# PAGE2.net
KiCad netlist of a schematic drawn in Altium Designer
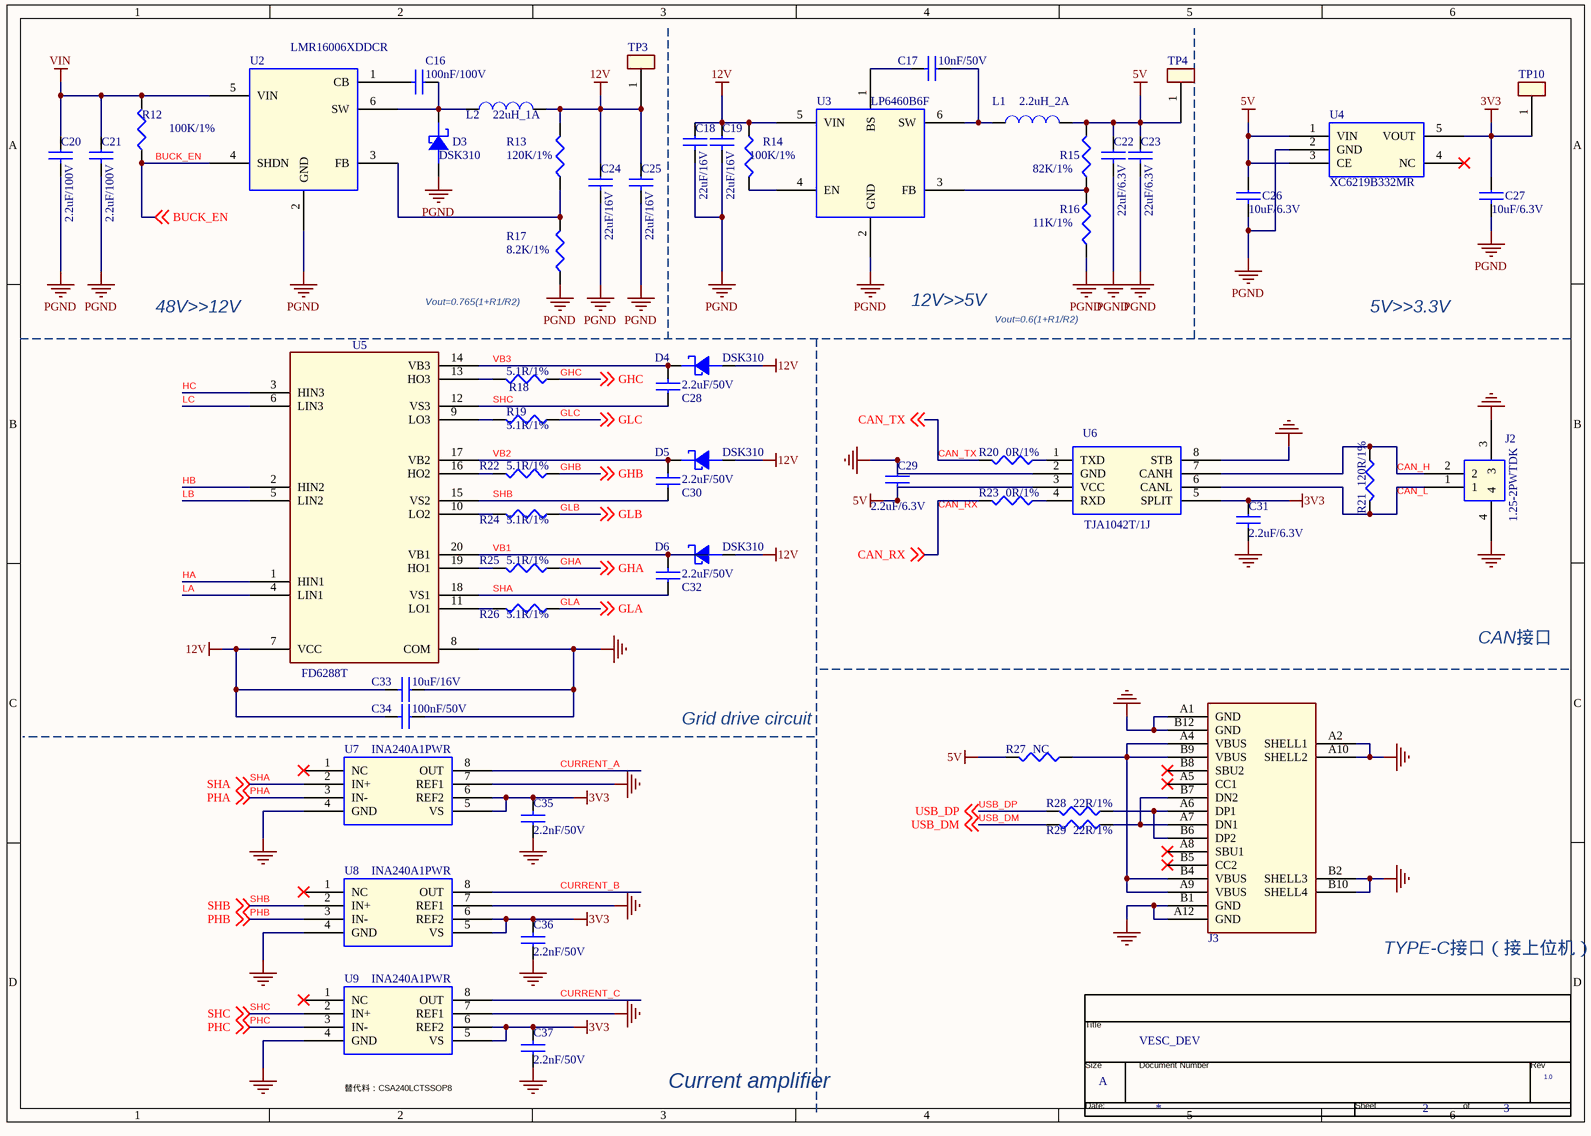
[diagram p0: PAGE2.SchDoc]

(export (version "E")
  (design (tool "Eeschema 10.0.6"))
  (components
    (comp (ref "*")
      (value "TitleBlock0")
      (fields
        (field (name "PAGE COUNT") "3")
        (field (name "PAGE NUMBER") "2")
        (field (name "PAGE SIZE") "A")
        (field (name "TITLE") "VESC_DEV")
        (field (name "REVCODE") "1.0")
      )
      (libsource (lib "*") (part "TitleBlock0"))
    )
    (comp (ref "C16") (value "100nF/100V") (footprint "C0603") (libsource (lib "*") (part "CAP NP")))
    (comp (ref "C17") (value "10nF/50V") (footprint "C0402") (libsource (lib "*") (part "CAP NP")))
    (comp (ref "C18") (value "22uF/16V") (footprint "C0805") (libsource (lib "*") (part "CAP NP")))
    (comp (ref "C19") (value "22uF/16V") (footprint "C0805") (libsource (lib "*") (part "CAP NP")))
    (comp (ref "C20") (value "2.2uF/100V") (footprint "C1206") (libsource (lib "*") (part "CAP NP")))
    (comp (ref "C21") (value "2.2uF/100V") (footprint "C1206") (libsource (lib "*") (part "CAP NP")))
    (comp (ref "C22") (value "22uF/6.3V") (footprint "C0805") (libsource (lib "*") (part "CAP NP")))
    (comp (ref "C23") (value "22uF/6.3V") (footprint "C0805") (libsource (lib "*") (part "CAP NP")))
    (comp (ref "C24") (value "22uF/16V") (footprint "C0805") (libsource (lib "*") (part "CAP NP")))
    (comp (ref "C25") (value "22uF/16V") (footprint "C0805") (libsource (lib "*") (part "CAP NP")))
    (comp (ref "C26") (value "10uF/6.3V") (footprint "C0402") (libsource (lib "*") (part "CAP NP")))
    (comp (ref "C27") (value "10uF/6.3V") (footprint "C0402") (libsource (lib "*") (part "CAP NP")))
    (comp (ref "C28") (value "2.2uF/50V") (footprint "C0603") (libsource (lib "*") (part "CAP NP")))
    (comp (ref "C29") (value "2.2uF/6.3V") (footprint "C0402") (libsource (lib "*") (part "CAP NP")))
    (comp (ref "C30") (value "2.2uF/50V") (footprint "C0603") (libsource (lib "*") (part "CAP NP")))
    (comp (ref "C31") (value "2.2uF/6.3V") (footprint "C0402") (libsource (lib "*") (part "CAP NP")))
    (comp (ref "C32") (value "2.2uF/50V") (footprint "C0603") (libsource (lib "*") (part "CAP NP")))
    (comp (ref "C33") (value "10uF/16V") (footprint "C0603") (libsource (lib "*") (part "CAP NP")))
    (comp (ref "C34") (value "100nF/50V") (footprint "C0402") (libsource (lib "*") (part "CAP NP")))
    (comp (ref "C35") (value "2.2nF/50V") (footprint "C0402") (libsource (lib "*") (part "CAP NP")))
    (comp (ref "C36") (value "2.2nF/50V") (footprint "C0402") (libsource (lib "*") (part "CAP NP")))
    (comp (ref "C37") (value "2.2nF/50V") (footprint "C0402") (libsource (lib "*") (part "CAP NP")))
    (comp (ref "D3") (value "DSK310") (footprint "SOD-123F") (libsource (lib "*") (part "DIODE SCHOTTKY21")))
    (comp (ref "D4") (value "DSK310") (footprint "SOD-123F") (libsource (lib "*") (part "DIODE SCHOTTKY21")))
    (comp (ref "D5") (value "DSK310") (footprint "SOD-123F") (libsource (lib "*") (part "DIODE SCHOTTKY21")))
    (comp (ref "D6") (value "DSK310") (footprint "SOD-123F") (libsource (lib "*") (part "DIODE SCHOTTKY21")))
    (comp (ref "J2")
      (value "1.25-2PWTDK")
      (footprint "SMD-2P-1_25")
      (libsource (lib "*") (part "1.25-2PWTDK"))
    )
    (comp (ref "J3")
      (value "TYPE-C 16PLC-H10.0")
      (footprint "TYPE-C-TH_16PLC-H10.0")
      (description "连接器类型:Type-C;标准:USB 3.1;公母:母;安装方式:直插;触点数量:16P;端口数量:1;额定电流 - 电源:5A;触头材质:-;触头镀层:-;工作温度范围:-40℃~+85℃;")
      (fields (field (name "MANUFACTURER") "SHOU HAN(首韩)"))
      (libsource (lib "VESC_DEVICE_Library") (part "TYPE-C 16PLC-H10.0"))
    )
    (comp (ref "L1") (value "2.2uH_2A") (footprint "L4020") (libsource (lib "*") (part "INDUCTOR")))
    (comp (ref "L2") (value "22uH_1A") (footprint "L4020") (libsource (lib "*") (part "INDUCTOR")))
    (comp (ref "R12") (value "100K/1%") (footprint "R0402") (libsource (lib "*") (part "RESISTOR")))
    (comp (ref "R13") (value "120K/1%") (footprint "R0402") (libsource (lib "*") (part "RESISTOR")))
    (comp (ref "R14") (value "100K/1%") (footprint "R0402") (libsource (lib "*") (part "RESISTOR")))
    (comp (ref "R15") (value "82K/1%") (footprint "R0402") (libsource (lib "*") (part "RESISTOR")))
    (comp (ref "R16") (value "11K/1%") (footprint "R0402") (libsource (lib "*") (part "RESISTOR")))
    (comp (ref "R17") (value "8.2K/1%") (footprint "R0402") (libsource (lib "*") (part "RESISTOR")))
    (comp (ref "R18") (value "5.1R/1%") (footprint "R0402") (libsource (lib "*") (part "RESISTOR")))
    (comp (ref "R19") (value "5.1R/1%") (footprint "R0402") (libsource (lib "*") (part "RESISTOR")))
    (comp (ref "R20") (value "0R/1%") (footprint "R0402") (libsource (lib "*") (part "RESISTOR")))
    (comp (ref "R21") (value "120R/1%") (footprint "R0402") (libsource (lib "*") (part "RESISTOR")))
    (comp (ref "R22") (value "5.1R/1%") (footprint "R0402") (libsource (lib "*") (part "RESISTOR")))
    (comp (ref "R23") (value "0R/1%") (footprint "R0402") (libsource (lib "*") (part "RESISTOR")))
    (comp (ref "R24") (value "5.1R/1%") (footprint "R0402") (libsource (lib "*") (part "RESISTOR")))
    (comp (ref "R25") (value "5.1R/1%") (footprint "R0402") (libsource (lib "*") (part "RESISTOR")))
    (comp (ref "R26") (value "5.1R/1%") (footprint "R0402") (libsource (lib "*") (part "RESISTOR")))
    (comp (ref "R27") (value "NC") (footprint "R0603") (libsource (lib "*") (part "RESISTOR")))
    (comp (ref "R28") (value "22R/1%") (footprint "R0402") (libsource (lib "*") (part "RESISTOR")))
    (comp (ref "R29") (value "22R/1%") (footprint "R0402") (libsource (lib "*") (part "RESISTOR")))
    (comp (ref "TP3")
      (value "TEST POINT")
      (footprint "test_point_100_smd")
      (libsource (lib "VESC_DEVICE_Library") (part "TEST POINT"))
    )
    (comp (ref "TP4")
      (value "TEST POINT")
      (footprint "test_point_100_smd")
      (libsource (lib "VESC_DEVICE_Library") (part "TEST POINT"))
    )
    (comp (ref "TP10")
      (value "TEST POINT")
      (footprint "test_point_100_smd")
      (libsource (lib "VESC_DEVICE_Library") (part "TEST POINT"))
    )
    (comp (ref "U2")
      (value "LMR16006XDDCR")
      (footprint "SOT-23-6")
      (libsource (lib "*") (part "LMR16006XDDCR"))
    )
    (comp (ref "U3") (value "LP6460B6F") (footprint "SOT-23-6") (libsource (lib "*") (part "LP6460B6F")))
    (comp (ref "U4")
      (value "XC6219B332MR")
      (footprint "SOT-23-5")
      (libsource (lib "*") (part "XC6219B332MR"))
    )
    (comp (ref "U5")
      (value "FD6288T")
      (footprint "TSSOP-20")
      (libsource (lib "VESC_DEVICE_Library") (part "FD6288T"))
    )
    (comp (ref "U6") (value "TJA1042T/1J") (footprint "SOP-8") (libsource (lib "*") (part "TJA1042T/1J")))
    (comp (ref "U7") (value "INA240A1PWR") (footprint "TSSOP-8") (libsource (lib "*") (part "INA240A1PWR")))
    (comp (ref "U8") (value "INA240A1PWR") (footprint "TSSOP-8") (libsource (lib "*") (part "INA240A1PWR")))
    (comp (ref "U9") (value "INA240A1PWR") (footprint "TSSOP-8") (libsource (lib "*") (part "INA240A1PWR")))
  )
  (nets
    (net (code "1") (name "/CAN_H") (class "Default")
      (node (ref "J2") (pin "2") (pinfunction "2_2") (pintype "passive"))
      (node (ref "R21") (pin "1") (pinfunction "1_1") (pintype "passive"))
      (node (ref "U6") (pin "7") (pinfunction "CANH_7") (pintype "passive"))
    )
    (net (code "2") (name "/CAN_L") (class "Default")
      (node (ref "J2") (pin "1") (pinfunction "1_1") (pintype "passive"))
      (node (ref "R21") (pin "2") (pinfunction "2_2") (pintype "passive"))
      (node (ref "U6") (pin "6") (pinfunction "CANL_6") (pintype "passive"))
    )
    (net (code "3") (name "/CURRENT_A") (class "Default")
      (node (ref "U7") (pin "8") (pinfunction "OUT_8") (pintype "passive"))
    )
    (net (code "4") (name "/CURRENT_B") (class "Default")
      (node (ref "U8") (pin "8") (pinfunction "OUT_8") (pintype "passive"))
    )
    (net (code "5") (name "/CURRENT_C") (class "Default")
      (node (ref "U9") (pin "8") (pinfunction "OUT_8") (pintype "passive"))
    )
    (net (code "6") (name "/HA") (class "Default")
      (node (ref "U5") (pin "1") (pinfunction "HIN1_1") (pintype "passive"))
    )
    (net (code "7") (name "/HB") (class "Default")
      (node (ref "U5") (pin "2") (pinfunction "HIN2_2") (pintype "passive"))
    )
    (net (code "8") (name "/HC") (class "Default")
      (node (ref "U5") (pin "3") (pinfunction "HIN3_3") (pintype "passive"))
    )
    (net (code "9") (name "/LA") (class "Default")
      (node (ref "U5") (pin "4") (pinfunction "LIN1_4") (pintype "passive"))
    )
    (net (code "10") (name "/LB") (class "Default")
      (node (ref "U5") (pin "5") (pinfunction "LIN2_5") (pintype "passive"))
    )
    (net (code "11") (name "/LC") (class "Default")
      (node (ref "U5") (pin "6") (pinfunction "LIN3_6") (pintype "passive"))
    )
    (net (code "12") (name "/VB1") (class "Default")
      (node (ref "C32") (pin "2") (pinfunction "2_2") (pintype "passive"))
      (node (ref "D6") (pin "1") (pinfunction "K_1") (pintype "passive"))
      (node (ref "U5") (pin "20") (pinfunction "VB1_20") (pintype "passive"))
    )
    (net (code "13") (name "/VB2") (class "Default")
      (node (ref "C30") (pin "2") (pinfunction "2_2") (pintype "passive"))
      (node (ref "D5") (pin "1") (pinfunction "K_1") (pintype "passive"))
      (node (ref "U5") (pin "17") (pinfunction "VB2_17") (pintype "passive"))
    )
    (net (code "14") (name "/VB3") (class "Default")
      (node (ref "C28") (pin "2") (pinfunction "2_2") (pintype "passive"))
      (node (ref "D4") (pin "1") (pinfunction "K_1") (pintype "passive"))
      (node (ref "U5") (pin "14") (pinfunction "VB3_14") (pintype "passive"))
    )
    (net (code "15") (name "3V3") (class "Default")
      (node (ref "C27") (pin "1") (pinfunction "1_1") (pintype "passive"))
      (node (ref "C31") (pin "1") (pinfunction "1_1") (pintype "passive"))
      (node (ref "C35") (pin "2") (pinfunction "2_2") (pintype "passive"))
      (node (ref "C36") (pin "2") (pinfunction "2_2") (pintype "passive"))
      (node (ref "C37") (pin "2") (pinfunction "2_2") (pintype "passive"))
      (node (ref "TP10") (pin "1") (pinfunction "1_1") (pintype "passive"))
      (node (ref "U4") (pin "5") (pinfunction "VOUT_5") (pintype "passive"))
      (node (ref "U6") (pin "5") (pinfunction "SPLIT_5") (pintype "passive"))
      (node (ref "U7") (pin "5") (pinfunction "VS_5") (pintype "passive"))
      (node (ref "U7") (pin "6") (pinfunction "REF2_6") (pintype "passive"))
      (node (ref "U8") (pin "5") (pinfunction "VS_5") (pintype "passive"))
      (node (ref "U8") (pin "6") (pinfunction "REF2_6") (pintype "passive"))
      (node (ref "U9") (pin "5") (pinfunction "VS_5") (pintype "passive"))
      (node (ref "U9") (pin "6") (pinfunction "REF2_6") (pintype "passive"))
    )
    (net (code "16") (name "5V") (class "Default")
      (node (ref "C22") (pin "1") (pinfunction "1_1") (pintype "passive"))
      (node (ref "C23") (pin "1") (pinfunction "1_1") (pintype "passive"))
      (node (ref "C26") (pin "1") (pinfunction "1_1") (pintype "passive"))
      (node (ref "C29") (pin "2") (pinfunction "2_2") (pintype "passive"))
      (node (ref "L1") (pin "2") (pinfunction "2_2") (pintype "passive"))
      (node (ref "R15") (pin "2") (pinfunction "2_2") (pintype "passive"))
      (node (ref "R27") (pin "2") (pinfunction "2_2") (pintype "passive"))
      (node (ref "TP4") (pin "1") (pinfunction "1_1") (pintype "passive"))
      (node (ref "U4") (pin "1") (pinfunction "VIN_1") (pintype "passive"))
      (node (ref "U4") (pin "3") (pinfunction "CE_3") (pintype "passive"))
      (node (ref "U6") (pin "3") (pinfunction "VCC_3") (pintype "passive"))
    )
    (net (code "17") (name "12V") (class "Default")
      (node (ref "C18") (pin "1") (pinfunction "1_1") (pintype "passive"))
      (node (ref "C19") (pin "1") (pinfunction "1_1") (pintype "passive"))
      (node (ref "C24") (pin "1") (pinfunction "1_1") (pintype "passive"))
      (node (ref "C25") (pin "1") (pinfunction "1_1") (pintype "passive"))
      (node (ref "C33") (pin "2") (pinfunction "2_2") (pintype "passive"))
      (node (ref "C34") (pin "2") (pinfunction "2_2") (pintype "passive"))
      (node (ref "D4") (pin "2") (pinfunction "A_2") (pintype "passive"))
      (node (ref "D5") (pin "2") (pinfunction "A_2") (pintype "passive"))
      (node (ref "D6") (pin "2") (pinfunction "A_2") (pintype "passive"))
      (node (ref "L2") (pin "2") (pinfunction "2_2") (pintype "passive"))
      (node (ref "R13") (pin "2") (pinfunction "2_2") (pintype "passive"))
      (node (ref "R14") (pin "1") (pinfunction "1_1") (pintype "passive"))
      (node (ref "TP3") (pin "1") (pinfunction "1_1") (pintype "passive"))
      (node (ref "U3") (pin "5") (pinfunction "VIN_5") (pintype "passive"))
      (node (ref "U5") (pin "7") (pinfunction "VCC_7") (pintype "power_in"))
    )
    (net (code "18") (name "BUCK_EN") (class "Default")
      (node (ref "R12") (pin "1") (pinfunction "1_1") (pintype "passive"))
      (node (ref "U2") (pin "4") (pinfunction "SHDN_4") (pintype "passive"))
    )
    (net (code "19") (name "CAN_RX") (class "Default")
      (node (ref "R23") (pin "2") (pinfunction "2_2") (pintype "passive"))
    )
    (net (code "20") (name "CAN_TX") (class "Default")
      (node (ref "R20") (pin "2") (pinfunction "2_2") (pintype "passive"))
    )
    (net (code "21") (name "GHA") (class "Default")
      (node (ref "R25") (pin "1") (pinfunction "1_1") (pintype "passive"))
    )
    (net (code "22") (name "GHB") (class "Default")
      (node (ref "R22") (pin "1") (pinfunction "1_1") (pintype "passive"))
    )
    (net (code "23") (name "GHC") (class "Default")
      (node (ref "R18") (pin "1") (pinfunction "1_1") (pintype "passive"))
    )
    (net (code "24") (name "GLA") (class "Default")
      (node (ref "R26") (pin "1") (pinfunction "1_1") (pintype "passive"))
    )
    (net (code "25") (name "GLB") (class "Default")
      (node (ref "R24") (pin "1") (pinfunction "1_1") (pintype "passive"))
    )
    (net (code "26") (name "GLC") (class "Default")
      (node (ref "R19") (pin "1") (pinfunction "1_1") (pintype "passive"))
    )
    (net (code "27") (name "GND") (class "Default")
      (node (ref "C29") (pin "1") (pinfunction "1_1") (pintype "passive"))
      (node (ref "C31") (pin "2") (pinfunction "2_2") (pintype "passive"))
      (node (ref "C33") (pin "1") (pinfunction "1_1") (pintype "passive"))
      (node (ref "C34") (pin "1") (pinfunction "1_1") (pintype "passive"))
      (node (ref "C35") (pin "1") (pinfunction "1_1") (pintype "passive"))
      (node (ref "C36") (pin "1") (pinfunction "1_1") (pintype "passive"))
      (node (ref "C37") (pin "1") (pinfunction "1_1") (pintype "passive"))
      (node (ref "J2") (pin "3") (pinfunction "3_3") (pintype "passive"))
      (node (ref "J2") (pin "4") (pinfunction "4_4") (pintype "passive"))
      (node (ref "J3") (pin "A1") (pinfunction "GND_A1") (pintype "power_in"))
      (node (ref "J3") (pin "A10") (pinfunction "SHELL2_A10") (pintype "power_in"))
      (node (ref "J3") (pin "A12") (pinfunction "GND_A12") (pintype "power_in"))
      (node (ref "J3") (pin "A2") (pinfunction "SHELL1_A2") (pintype "power_in"))
      (node (ref "J3") (pin "B1") (pinfunction "GND_B1") (pintype "power_in"))
      (node (ref "J3") (pin "B10") (pinfunction "SHELL4_B10") (pintype "power_in"))
      (node (ref "J3") (pin "B12") (pinfunction "GND_B12") (pintype "power_in"))
      (node (ref "J3") (pin "B2") (pinfunction "SHELL3_B2") (pintype "power_in"))
      (node (ref "U5") (pin "8") (pinfunction "COM_8") (pintype "power_in"))
      (node (ref "U6") (pin "2") (pinfunction "GND_2") (pintype "passive"))
      (node (ref "U6") (pin "8") (pinfunction "STB_8") (pintype "passive"))
      (node (ref "U7") (pin "4") (pinfunction "GND_4") (pintype "passive"))
      (node (ref "U7") (pin "7") (pinfunction "REF1_7") (pintype "passive"))
      (node (ref "U8") (pin "4") (pinfunction "GND_4") (pintype "passive"))
      (node (ref "U8") (pin "7") (pinfunction "REF1_7") (pintype "passive"))
      (node (ref "U9") (pin "4") (pinfunction "GND_4") (pintype "passive"))
      (node (ref "U9") (pin "7") (pinfunction "REF1_7") (pintype "passive"))
    )
    (net (code "28") (name "Net-(D3-K)") (class "Default")
      (node (ref "C16") (pin "1") (pinfunction "1_1") (pintype "passive"))
      (node (ref "D3") (pin "1") (pinfunction "K_1") (pintype "passive"))
      (node (ref "L2") (pin "1") (pinfunction "1_1") (pintype "passive"))
      (node (ref "U2") (pin "6") (pinfunction "SW_6") (pintype "passive"))
    )
    (net (code "29") (name "Net-(J3-DN1)") (class "Default")
      (node (ref "J3") (pin "A7") (pinfunction "DN1_A7") (pintype "passive"))
      (node (ref "J3") (pin "B7") (pinfunction "DN2_B7") (pintype "passive"))
      (node (ref "R29") (pin "1") (pinfunction "1_1") (pintype "passive"))
    )
    (net (code "30") (name "Net-(J3-DP1)") (class "Default")
      (node (ref "J3") (pin "A6") (pinfunction "DP1_A6") (pintype "passive"))
      (node (ref "J3") (pin "B6") (pinfunction "DP2_B6") (pintype "passive"))
      (node (ref "R28") (pin "1") (pinfunction "1_1") (pintype "passive"))
    )
    (net (code "31") (name "Net-(J3-VBUS-PadA4)") (class "Default")
      (node (ref "J3") (pin "A4") (pinfunction "VBUS_A4") (pintype "power_in"))
      (node (ref "J3") (pin "A9") (pinfunction "VBUS_A9") (pintype "power_in"))
      (node (ref "J3") (pin "B4") (pinfunction "VBUS_B4") (pintype "power_in"))
      (node (ref "J3") (pin "B9") (pinfunction "VBUS_B9") (pintype "power_in"))
      (node (ref "R27") (pin "1") (pinfunction "1_1") (pintype "passive"))
    )
    (net (code "32") (name "Net-(U2-CB)") (class "Default")
      (node (ref "C16") (pin "2") (pinfunction "2_2") (pintype "passive"))
      (node (ref "U2") (pin "1") (pinfunction "CB_1") (pintype "passive"))
    )
    (net (code "33") (name "Net-(U2-FB)") (class "Default")
      (node (ref "R13") (pin "1") (pinfunction "1_1") (pintype "passive"))
      (node (ref "R17") (pin "2") (pinfunction "2_2") (pintype "passive"))
      (node (ref "U2") (pin "3") (pinfunction "FB_3") (pintype "passive"))
    )
    (net (code "34") (name "Net-(U3-BS)") (class "Default")
      (node (ref "C17") (pin "2") (pinfunction "2_2") (pintype "passive"))
      (node (ref "U3") (pin "1") (pinfunction "BS_1") (pintype "passive"))
    )
    (net (code "35") (name "Net-(U3-EN)") (class "Default")
      (node (ref "R14") (pin "2") (pinfunction "2_2") (pintype "passive"))
      (node (ref "U3") (pin "4") (pinfunction "EN_4") (pintype "passive"))
    )
    (net (code "36") (name "Net-(U3-FB)") (class "Default")
      (node (ref "R15") (pin "1") (pinfunction "1_1") (pintype "passive"))
      (node (ref "R16") (pin "2") (pinfunction "2_2") (pintype "passive"))
      (node (ref "U3") (pin "3") (pinfunction "FB_3") (pintype "passive"))
    )
    (net (code "37") (name "Net-(U3-SW)") (class "Default")
      (node (ref "C17") (pin "1") (pinfunction "1_1") (pintype "passive"))
      (node (ref "L1") (pin "1") (pinfunction "1_1") (pintype "passive"))
      (node (ref "U3") (pin "6") (pinfunction "SW_6") (pintype "passive"))
    )
    (net (code "38") (name "Net-(U5-HO1)") (class "Default")
      (node (ref "R25") (pin "2") (pinfunction "2_2") (pintype "passive"))
      (node (ref "U5") (pin "19") (pinfunction "HO1_19") (pintype "passive"))
    )
    (net (code "39") (name "Net-(U5-HO2)") (class "Default")
      (node (ref "R22") (pin "2") (pinfunction "2_2") (pintype "passive"))
      (node (ref "U5") (pin "16") (pinfunction "HO2_16") (pintype "passive"))
    )
    (net (code "40") (name "Net-(U5-HO3)") (class "Default")
      (node (ref "R18") (pin "2") (pinfunction "2_2") (pintype "passive"))
      (node (ref "U5") (pin "13") (pinfunction "HO3_13") (pintype "passive"))
    )
    (net (code "41") (name "Net-(U5-LO1)") (class "Default")
      (node (ref "R26") (pin "2") (pinfunction "2_2") (pintype "passive"))
      (node (ref "U5") (pin "11") (pinfunction "LO1_11") (pintype "passive"))
    )
    (net (code "42") (name "Net-(U5-LO2)") (class "Default")
      (node (ref "R24") (pin "2") (pinfunction "2_2") (pintype "passive"))
      (node (ref "U5") (pin "10") (pinfunction "LO2_10") (pintype "passive"))
    )
    (net (code "43") (name "Net-(U5-LO3)") (class "Default")
      (node (ref "R19") (pin "2") (pinfunction "2_2") (pintype "passive"))
      (node (ref "U5") (pin "9") (pinfunction "LO3_9") (pintype "passive"))
    )
    (net (code "44") (name "Net-(U6-RXD)") (class "Default")
      (node (ref "R23") (pin "1") (pinfunction "1_1") (pintype "passive"))
      (node (ref "U6") (pin "4") (pinfunction "RXD_4") (pintype "passive"))
    )
    (net (code "45") (name "Net-(U6-TXD)") (class "Default")
      (node (ref "R20") (pin "1") (pinfunction "1_1") (pintype "passive"))
      (node (ref "U6") (pin "1") (pinfunction "TXD_1") (pintype "passive"))
    )
    (net (code "46") (name "PGND") (class "Default")
      (node (ref "C18") (pin "2") (pinfunction "2_2") (pintype "passive"))
      (node (ref "C19") (pin "2") (pinfunction "2_2") (pintype "passive"))
      (node (ref "C20") (pin "2") (pinfunction "2_2") (pintype "passive"))
      (node (ref "C21") (pin "2") (pinfunction "2_2") (pintype "passive"))
      (node (ref "C22") (pin "2") (pinfunction "2_2") (pintype "passive"))
      (node (ref "C23") (pin "2") (pinfunction "2_2") (pintype "passive"))
      (node (ref "C24") (pin "2") (pinfunction "2_2") (pintype "passive"))
      (node (ref "C25") (pin "2") (pinfunction "2_2") (pintype "passive"))
      (node (ref "C26") (pin "2") (pinfunction "2_2") (pintype "passive"))
      (node (ref "C27") (pin "2") (pinfunction "2_2") (pintype "passive"))
      (node (ref "D3") (pin "2") (pinfunction "A_2") (pintype "passive"))
      (node (ref "R16") (pin "1") (pinfunction "1_1") (pintype "passive"))
      (node (ref "R17") (pin "1") (pinfunction "1_1") (pintype "passive"))
      (node (ref "U2") (pin "2") (pinfunction "GND_2") (pintype "passive"))
      (node (ref "U3") (pin "2") (pinfunction "GND_2") (pintype "passive"))
      (node (ref "U4") (pin "2") (pinfunction "GND_2") (pintype "passive"))
    )
    (net (code "47") (name "PHA") (class "Default")
      (node (ref "U7") (pin "3") (pinfunction "IN-_3") (pintype "passive"))
    )
    (net (code "48") (name "PHB") (class "Default")
      (node (ref "U8") (pin "3") (pinfunction "IN-_3") (pintype "passive"))
    )
    (net (code "49") (name "PHC") (class "Default")
      (node (ref "U9") (pin "3") (pinfunction "IN-_3") (pintype "passive"))
    )
    (net (code "50") (name "SHA") (class "Default")
      (node (ref "C32") (pin "1") (pinfunction "1_1") (pintype "passive"))
      (node (ref "U5") (pin "18") (pinfunction "VS1_18") (pintype "passive"))
      (node (ref "U7") (pin "2") (pinfunction "IN+_2") (pintype "passive"))
    )
    (net (code "51") (name "SHB") (class "Default")
      (node (ref "C30") (pin "1") (pinfunction "1_1") (pintype "passive"))
      (node (ref "U5") (pin "15") (pinfunction "VS2_15") (pintype "passive"))
      (node (ref "U8") (pin "2") (pinfunction "IN+_2") (pintype "passive"))
    )
    (net (code "52") (name "SHC") (class "Default")
      (node (ref "C28") (pin "1") (pinfunction "1_1") (pintype "passive"))
      (node (ref "U5") (pin "12") (pinfunction "VS3_12") (pintype "passive"))
      (node (ref "U9") (pin "2") (pinfunction "IN+_2") (pintype "passive"))
    )
    (net (code "53") (name "USB_DM") (class "Default")
      (node (ref "R29") (pin "2") (pinfunction "2_2") (pintype "passive"))
    )
    (net (code "54") (name "USB_DP") (class "Default")
      (node (ref "R28") (pin "2") (pinfunction "2_2") (pintype "passive"))
    )
    (net (code "55") (name "VIN") (class "Default")
      (node (ref "C20") (pin "1") (pinfunction "1_1") (pintype "passive"))
      (node (ref "C21") (pin "1") (pinfunction "1_1") (pintype "passive"))
      (node (ref "R12") (pin "2") (pinfunction "2_2") (pintype "passive"))
      (node (ref "U2") (pin "5") (pinfunction "VIN_5") (pintype "passive"))
    )
    (net (code "56") (name "unconnected-(J3-CC1-PadA5)") (class "Default")
      (node (ref "J3") (pin "A5") (pinfunction "CC1_A5") (pintype "passive+no_connect"))
    )
    (net (code "57") (name "unconnected-(J3-CC2-PadB5)") (class "Default")
      (node (ref "J3") (pin "B5") (pinfunction "CC2_B5") (pintype "passive+no_connect"))
    )
    (net (code "58") (name "unconnected-(J3-SBU1-PadA8)") (class "Default")
      (node (ref "J3") (pin "A8") (pinfunction "SBU1_A8") (pintype "passive+no_connect"))
    )
    (net (code "59") (name "unconnected-(J3-SBU2-PadB8)") (class "Default")
      (node (ref "J3") (pin "B8") (pinfunction "SBU2_B8") (pintype "passive+no_connect"))
    )
    (net (code "60") (name "unconnected-(U4-NC-Pad4)") (class "Default")
      (node (ref "U4") (pin "4") (pinfunction "NC_4") (pintype "passive+no_connect"))
    )
    (net (code "61") (name "unconnected-(U7-NC-Pad1)") (class "Default")
      (node (ref "U7") (pin "1") (pinfunction "NC_1") (pintype "passive+no_connect"))
    )
    (net (code "62") (name "unconnected-(U8-NC-Pad1)") (class "Default")
      (node (ref "U8") (pin "1") (pinfunction "NC_1") (pintype "passive+no_connect"))
    )
    (net (code "63") (name "unconnected-(U9-NC-Pad1)") (class "Default")
      (node (ref "U9") (pin "1") (pinfunction "NC_1") (pintype "passive+no_connect"))
    )
  )
)
